# Humidifier.net
KiCad netlist of a schematic drawn in Altium Designer
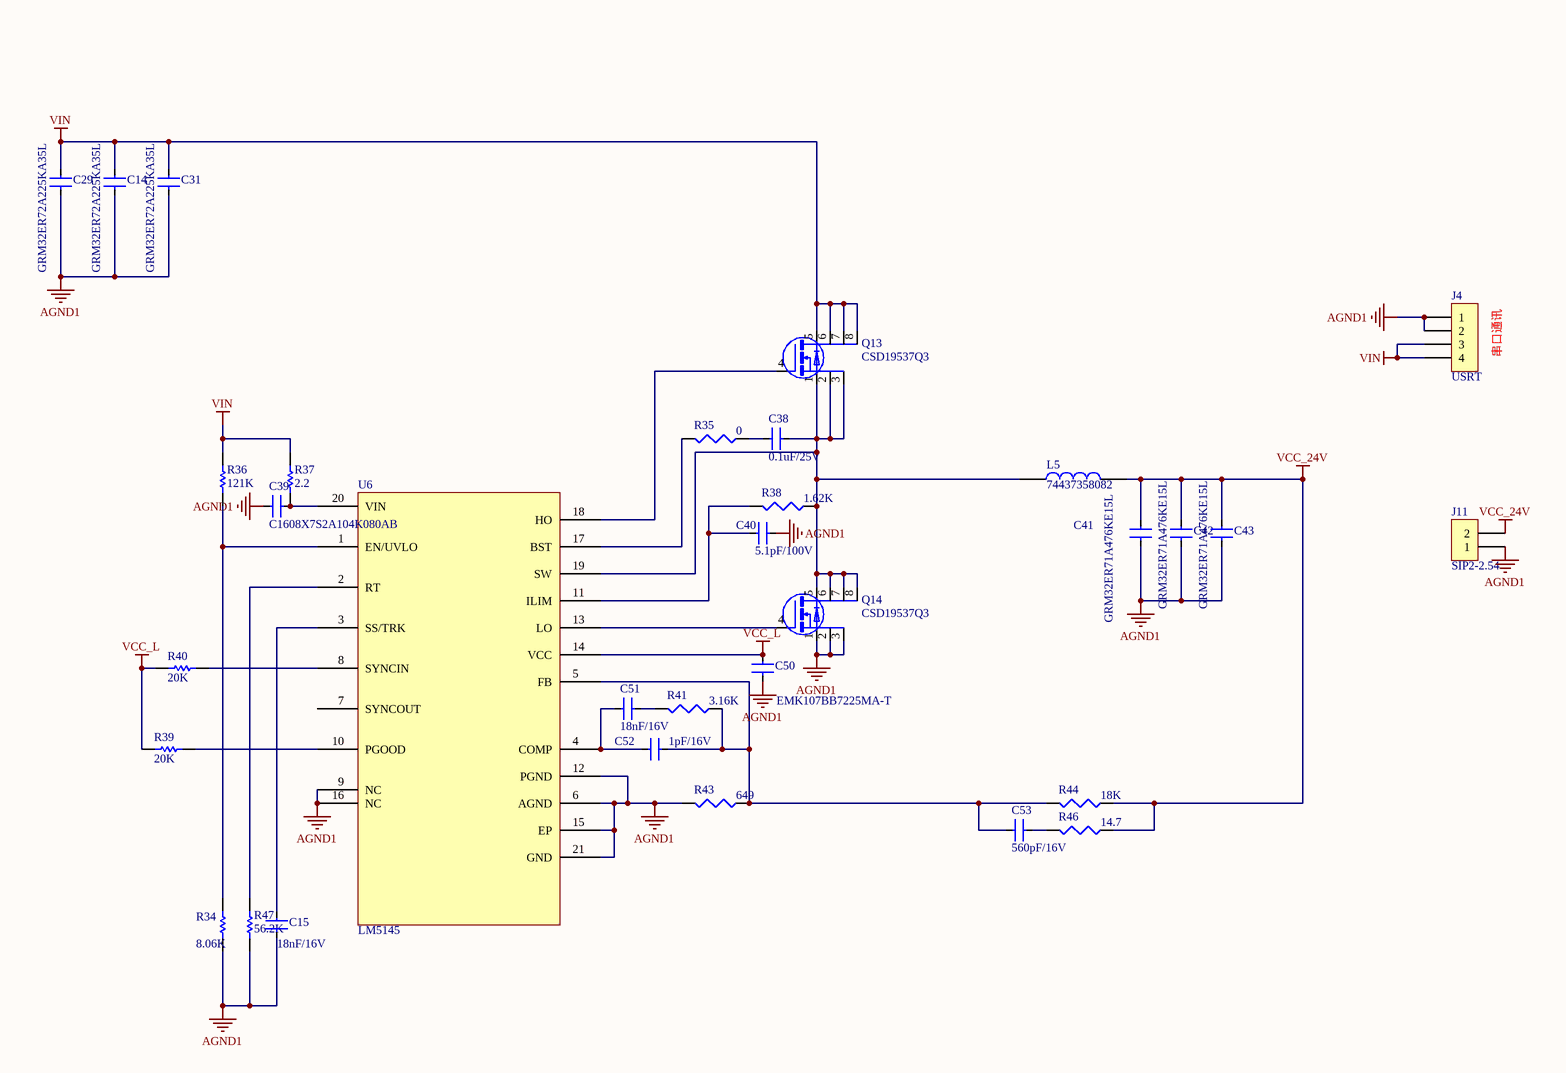
[diagram p0: Humidifier.SchDoc]

(export (version "E")
  (design (tool "Eeschema 10.0.6"))
  (components
    (comp (ref "C14")
      (value "GRM32ER72A225KA35L")
      (footprint "1210C")
      (description "CCX85-103")
      (libsource (lib "无极性电容") (part "0.01UF"))
    )
    (comp (ref "C15")
      (value "18nF/16V")
      (footprint "0603C")
      (description "CCX85-103")
      (libsource (lib "无极性电容") (part "0.01UF"))
    )
    (comp (ref "C29")
      (value "GRM32ER72A225KA35L")
      (footprint "1210C")
      (description "CCX85-103")
      (libsource (lib "无极性电容") (part "0.01UF"))
    )
    (comp (ref "C31")
      (value "GRM32ER72A225KA35L")
      (footprint "1210C")
      (description "CCX85-103")
      (libsource (lib "无极性电容") (part "0.01UF"))
    )
    (comp (ref "C38")
      (value "0.1uF/25V")
      (footprint "0603C")
      (description "CCX85-103")
      (libsource (lib "无极性电容") (part "0.01UF"))
    )
    (comp (ref "C39")
      (value "C1608X7S2A104K080AB")
      (footprint "0603C")
      (description "CCX85-103")
      (libsource (lib "无极性电容") (part "0.01UF"))
    )
    (comp (ref "C40")
      (value "5.1pF/100V")
      (footprint "0603C")
      (description "CCX85-103")
      (libsource (lib "无极性电容") (part "0.01UF"))
    )
    (comp (ref "C41")
      (value "GRM32ER71A476KE15L")
      (footprint "1210C")
      (description "CCX85-103")
      (libsource (lib "无极性电容") (part "0.01UF"))
    )
    (comp (ref "C42")
      (value "GRM32ER71A476KE15L")
      (footprint "1210C")
      (description "CCX85-103")
      (libsource (lib "无极性电容") (part "0.01UF"))
    )
    (comp (ref "C43")
      (value "GRM32ER71A476KE15L")
      (footprint "1210C")
      (description "CCX85-103")
      (libsource (lib "无极性电容") (part "0.01UF"))
    )
    (comp (ref "C50")
      (value "EMK107BB7225MA-T")
      (footprint "0603C")
      (description "CCX85-103")
      (libsource (lib "无极性电容") (part "0.01UF"))
    )
    (comp (ref "C51")
      (value "18nF/16V")
      (footprint "0603C")
      (description "CCX85-103")
      (libsource (lib "无极性电容") (part "0.01UF"))
    )
    (comp (ref "C52")
      (value "1pF/16V")
      (footprint "0603C")
      (description "CCX85-103")
      (libsource (lib "无极性电容") (part "0.01UF"))
    )
    (comp (ref "C53")
      (value "560pF/16V")
      (footprint "0603C")
      (description "CCX85-103")
      (libsource (lib "无极性电容") (part "0.01UF"))
    )
    (comp (ref "J4")
      (value "USRT")
      (footprint "hdr1x4")
      (description "CN-SIP4-2.54")
      (libsource (lib "接插件") (part "SIP4-2.54"))
    )
    (comp (ref "J11")
      (value "SIP2-2.54")
      (footprint "SIP-2L")
      (description "CN-SIP2-2.54")
      (libsource (lib "接插件") (part "SIP2-2.54"))
    )
    (comp (ref "L5") (value "74437358082") (footprint "SRP1270-2R2M") (libsource (lib "*") (part "INDUCTOR")))
    (comp (ref "Q13")
      (value "CSD19537Q3")
      (footprint "PowerPAK SO-8")
      (description "Si4004DY")
      (libsource (lib "Schlib_20110825") (part "Si4004DY"))
    )
    (comp (ref "Q14")
      (value "CSD19537Q3")
      (footprint "PowerPAK SO-8")
      (description "Si4004DY")
      (libsource (lib "Schlib_20110825") (part "Si4004DY"))
    )
    (comp (ref "R34")
      (value "8.06K")
      (footprint "0603R")
      (description "Semiconductor Resistor")
      (fields (field (name "PUBLISHER") "Altium Limited"))
      (libsource (lib "Miscellaneous Devices") (part "Res Semi"))
    )
    (comp (ref "R35")
      (value "0")
      (footprint "0603R")
      (description "Resistor")
      (fields (field (name "PUBLISHER") "Altium Limited"))
      (libsource (lib "SM") (part "Res3"))
    )
    (comp (ref "R36")
      (value "121K")
      (footprint "0805R")
      (description "Semiconductor Resistor")
      (fields (field (name "PUBLISHER") "Altium Limited"))
      (libsource (lib "Miscellaneous Devices") (part "Res Semi"))
    )
    (comp (ref "R37")
      (value "2.2")
      (footprint "0603R")
      (description "Semiconductor Resistor")
      (fields (field (name "PUBLISHER") "Altium Limited"))
      (libsource (lib "Miscellaneous Devices") (part "Res Semi"))
    )
    (comp (ref "R38")
      (value "1.62K")
      (footprint "0603R")
      (description "Resistor")
      (fields (field (name "PUBLISHER") "Altium Limited"))
      (libsource (lib "SM") (part "Res3"))
    )
    (comp (ref "R39")
      (value "20K")
      (footprint "0603R")
      (description "Semiconductor Resistor")
      (fields (field (name "PUBLISHER") "Altium Limited"))
      (libsource (lib "Miscellaneous Devices") (part "Res Semi"))
    )
    (comp (ref "R40")
      (value "20K")
      (footprint "0603R")
      (description "Semiconductor Resistor")
      (fields (field (name "PUBLISHER") "Altium Limited"))
      (libsource (lib "Miscellaneous Devices") (part "Res Semi"))
    )
    (comp (ref "R41")
      (value "3.16K")
      (footprint "0603R")
      (description "Resistor")
      (fields (field (name "PUBLISHER") "Altium Limited"))
      (libsource (lib "SM") (part "Res3"))
    )
    (comp (ref "R43")
      (value "649")
      (footprint "0603R")
      (description "Resistor")
      (fields (field (name "PUBLISHER") "Altium Limited"))
      (libsource (lib "SM") (part "Res3"))
    )
    (comp (ref "R44")
      (value "18K")
      (footprint "0603R")
      (description "Resistor")
      (fields (field (name "PUBLISHER") "Altium Limited"))
      (libsource (lib "SM") (part "Res3"))
    )
    (comp (ref "R46")
      (value "14.7")
      (footprint "0603R")
      (description "Resistor")
      (fields (field (name "PUBLISHER") "Altium Limited"))
      (libsource (lib "SM") (part "Res3"))
    )
    (comp (ref "R47")
      (value "56.2K")
      (footprint "0603R")
      (description "Semiconductor Resistor")
      (fields (field (name "PUBLISHER") "Altium Limited"))
      (libsource (lib "Miscellaneous Devices") (part "Res Semi"))
    )
    (comp (ref "U6")
      (value "LM5145")
      (footprint "QFN050P600-8N")
      (libsource (lib "Schlib_20110825") (part "LM5145"))
    )
  )
  (nets
    (net (code "1") (name "AGND1") (class "Default")
      (node (ref "C14") (pin "2") (pinfunction "2_2") (pintype "passive"))
      (node (ref "C15") (pin "2") (pinfunction "2_2") (pintype "passive"))
      (node (ref "C29") (pin "2") (pinfunction "2_2") (pintype "passive"))
      (node (ref "C31") (pin "2") (pinfunction "2_2") (pintype "passive"))
      (node (ref "C39") (pin "1") (pinfunction "1_1") (pintype "passive"))
      (node (ref "C40") (pin "1") (pinfunction "1_1") (pintype "passive"))
      (node (ref "C41") (pin "2") (pinfunction "2_2") (pintype "passive"))
      (node (ref "C42") (pin "2") (pinfunction "2_2") (pintype "passive"))
      (node (ref "C43") (pin "2") (pinfunction "2_2") (pintype "passive"))
      (node (ref "C50") (pin "2") (pinfunction "2_2") (pintype "passive"))
      (node (ref "J11") (pin "1") (pinfunction "1_1") (pintype "passive"))
      (node (ref "J4") (pin "1") (pinfunction "1_1") (pintype "passive"))
      (node (ref "J4") (pin "2") (pinfunction "2_2") (pintype "passive"))
      (node (ref "Q14") (pin "1") (pinfunction "S_1") (pintype "passive"))
      (node (ref "Q14") (pin "2") (pinfunction "S_2") (pintype "passive"))
      (node (ref "Q14") (pin "3") (pinfunction "S_3") (pintype "passive"))
      (node (ref "R34") (pin "1") (pinfunction "1_1") (pintype "passive"))
      (node (ref "R43") (pin "2") (pinfunction "2_2") (pintype "passive"))
      (node (ref "R47") (pin "1") (pinfunction "1_1") (pintype "passive"))
      (node (ref "U6") (pin "12") (pinfunction "PGND_12") (pintype "passive"))
      (node (ref "U6") (pin "15") (pinfunction "EP_15") (pintype "passive"))
      (node (ref "U6") (pin "16") (pinfunction "NC_16") (pintype "passive"))
      (node (ref "U6") (pin "21") (pinfunction "GND_21") (pintype "passive"))
      (node (ref "U6") (pin "6") (pinfunction "AGND_6") (pintype "passive"))
      (node (ref "U6") (pin "9") (pinfunction "NC_9") (pintype "passive"))
    )
    (net (code "2") (name "Net-(C38-Pad1)") (class "Default")
      (node (ref "C38") (pin "1") (pinfunction "1_1") (pintype "passive"))
      (node (ref "R35") (pin "1") (pinfunction "1_1") (pintype "passive"))
    )
    (net (code "3") (name "Net-(C51-Pad2)") (class "Default")
      (node (ref "C51") (pin "2") (pinfunction "2_2") (pintype "passive"))
      (node (ref "R41") (pin "2") (pinfunction "2_2") (pintype "passive"))
    )
    (net (code "4") (name "Net-(C53-Pad2)") (class "Default")
      (node (ref "C53") (pin "2") (pinfunction "2_2") (pintype "passive"))
      (node (ref "R46") (pin "2") (pinfunction "2_2") (pintype "passive"))
    )
    (net (code "5") (name "Net-(Q13-G)") (class "Default")
      (node (ref "Q13") (pin "4") (pinfunction "G_4") (pintype "passive"))
      (node (ref "U6") (pin "18") (pinfunction "HO_18") (pintype "passive"))
    )
    (net (code "6") (name "Net-(Q14-G)") (class "Default")
      (node (ref "Q14") (pin "4") (pinfunction "G_4") (pintype "passive"))
      (node (ref "U6") (pin "13") (pinfunction "LO_13") (pintype "passive"))
    )
    (net (code "7") (name "Net-(U6-BST)") (class "Default")
      (node (ref "R35") (pin "2") (pinfunction "2_2") (pintype "passive"))
      (node (ref "U6") (pin "17") (pinfunction "BST_17") (pintype "passive"))
    )
    (net (code "8") (name "Net-(U6-COMP)") (class "Default")
      (node (ref "C51") (pin "1") (pinfunction "1_1") (pintype "passive"))
      (node (ref "C52") (pin "1") (pinfunction "1_1") (pintype "passive"))
      (node (ref "U6") (pin "4") (pinfunction "COMP_4") (pintype "passive"))
    )
    (net (code "9") (name "Net-(U6-EN{slash}UVLO)") (class "Default")
      (node (ref "R34") (pin "2") (pinfunction "2_2") (pintype "passive"))
      (node (ref "R36") (pin "1") (pinfunction "1_1") (pintype "passive"))
      (node (ref "U6") (pin "1") (pinfunction "EN/UVLO_1") (pintype "passive"))
    )
    (net (code "10") (name "Net-(U6-FB)") (class "Default")
      (node (ref "C52") (pin "2") (pinfunction "2_2") (pintype "passive"))
      (node (ref "C53") (pin "1") (pinfunction "1_1") (pintype "passive"))
      (node (ref "R41") (pin "1") (pinfunction "1_1") (pintype "passive"))
      (node (ref "R43") (pin "1") (pinfunction "1_1") (pintype "passive"))
      (node (ref "R44") (pin "2") (pinfunction "2_2") (pintype "passive"))
      (node (ref "U6") (pin "5") (pinfunction "FB_5") (pintype "passive"))
    )
    (net (code "11") (name "Net-(U6-ILIM)") (class "Default")
      (node (ref "C40") (pin "2") (pinfunction "2_2") (pintype "passive"))
      (node (ref "R38") (pin "2") (pinfunction "2_2") (pintype "passive"))
      (node (ref "U6") (pin "11") (pinfunction "ILIM_11") (pintype "passive"))
    )
    (net (code "12") (name "Net-(U6-PGOOD)") (class "Default")
      (node (ref "R39") (pin "1") (pinfunction "1_1") (pintype "passive"))
      (node (ref "U6") (pin "10") (pinfunction "PGOOD_10") (pintype "passive"))
    )
    (net (code "13") (name "Net-(U6-RT)") (class "Default")
      (node (ref "R47") (pin "2") (pinfunction "2_2") (pintype "passive"))
      (node (ref "U6") (pin "2") (pinfunction "RT_2") (pintype "passive"))
    )
    (net (code "14") (name "Net-(U6-SS{slash}TRK)") (class "Default")
      (node (ref "C15") (pin "1") (pinfunction "1_1") (pintype "passive"))
      (node (ref "U6") (pin "3") (pinfunction "SS/TRK_3") (pintype "passive"))
    )
    (net (code "15") (name "Net-(U6-SW)") (class "Default")
      (node (ref "C38") (pin "2") (pinfunction "2_2") (pintype "passive"))
      (node (ref "L5") (pin "1") (pinfunction "1_1") (pintype "passive"))
      (node (ref "Q13") (pin "1") (pinfunction "S_1") (pintype "passive"))
      (node (ref "Q13") (pin "2") (pinfunction "S_2") (pintype "passive"))
      (node (ref "Q13") (pin "3") (pinfunction "S_3") (pintype "passive"))
      (node (ref "Q14") (pin "5") (pinfunction "D_5") (pintype "passive"))
      (node (ref "Q14") (pin "6") (pinfunction "D_6") (pintype "passive"))
      (node (ref "Q14") (pin "7") (pinfunction "D_7") (pintype "passive"))
      (node (ref "Q14") (pin "8") (pinfunction "D_8") (pintype "passive"))
      (node (ref "R38") (pin "1") (pinfunction "1_1") (pintype "passive"))
      (node (ref "U6") (pin "19") (pinfunction "SW_19") (pintype "passive"))
    )
    (net (code "16") (name "Net-(U6-SYNCIN)") (class "Default")
      (node (ref "R40") (pin "1") (pinfunction "1_1") (pintype "passive"))
      (node (ref "U6") (pin "8") (pinfunction "SYNCIN_8") (pintype "passive"))
    )
    (net (code "17") (name "Net-(U6-VIN)") (class "Default")
      (node (ref "C39") (pin "2") (pinfunction "2_2") (pintype "passive"))
      (node (ref "R37") (pin "2") (pinfunction "2_2") (pintype "passive"))
      (node (ref "U6") (pin "20") (pinfunction "VIN_20") (pintype "passive"))
    )
    (net (code "18") (name "VCC_24V") (class "Default")
      (node (ref "C41") (pin "1") (pinfunction "1_1") (pintype "passive"))
      (node (ref "C42") (pin "1") (pinfunction "1_1") (pintype "passive"))
      (node (ref "C43") (pin "1") (pinfunction "1_1") (pintype "passive"))
      (node (ref "J11") (pin "2") (pinfunction "2_2") (pintype "passive"))
      (node (ref "L5") (pin "2") (pinfunction "2_2") (pintype "passive"))
      (node (ref "R44") (pin "1") (pinfunction "1_1") (pintype "passive"))
      (node (ref "R46") (pin "1") (pinfunction "1_1") (pintype "passive"))
    )
    (net (code "19") (name "VCC_L") (class "Default")
      (node (ref "C50") (pin "1") (pinfunction "1_1") (pintype "passive"))
      (node (ref "R39") (pin "2") (pinfunction "2_2") (pintype "passive"))
      (node (ref "R40") (pin "2") (pinfunction "2_2") (pintype "passive"))
      (node (ref "U6") (pin "14") (pinfunction "VCC_14") (pintype "passive"))
    )
    (net (code "20") (name "VIN") (class "Default")
      (node (ref "C14") (pin "1") (pinfunction "1_1") (pintype "passive"))
      (node (ref "C29") (pin "1") (pinfunction "1_1") (pintype "passive"))
      (node (ref "C31") (pin "1") (pinfunction "1_1") (pintype "passive"))
      (node (ref "J4") (pin "3") (pinfunction "3_3") (pintype "passive"))
      (node (ref "J4") (pin "4") (pinfunction "4_4") (pintype "passive"))
      (node (ref "Q13") (pin "5") (pinfunction "D_5") (pintype "passive"))
      (node (ref "Q13") (pin "6") (pinfunction "D_6") (pintype "passive"))
      (node (ref "Q13") (pin "7") (pinfunction "D_7") (pintype "passive"))
      (node (ref "Q13") (pin "8") (pinfunction "D_8") (pintype "passive"))
      (node (ref "R36") (pin "2") (pinfunction "2_2") (pintype "passive"))
      (node (ref "R37") (pin "1") (pinfunction "1_1") (pintype "passive"))
    )
    (net (code "21") (name "unconnected-(U6-SYNCOUT-Pad7)") (class "Default")
      (node (ref "U6") (pin "7") (pinfunction "SYNCOUT_7") (pintype "passive"))
    )
  )
)
